# 01_Under_voltage_detection.net
KiCad netlist of a schematic drawn in Altium Designer
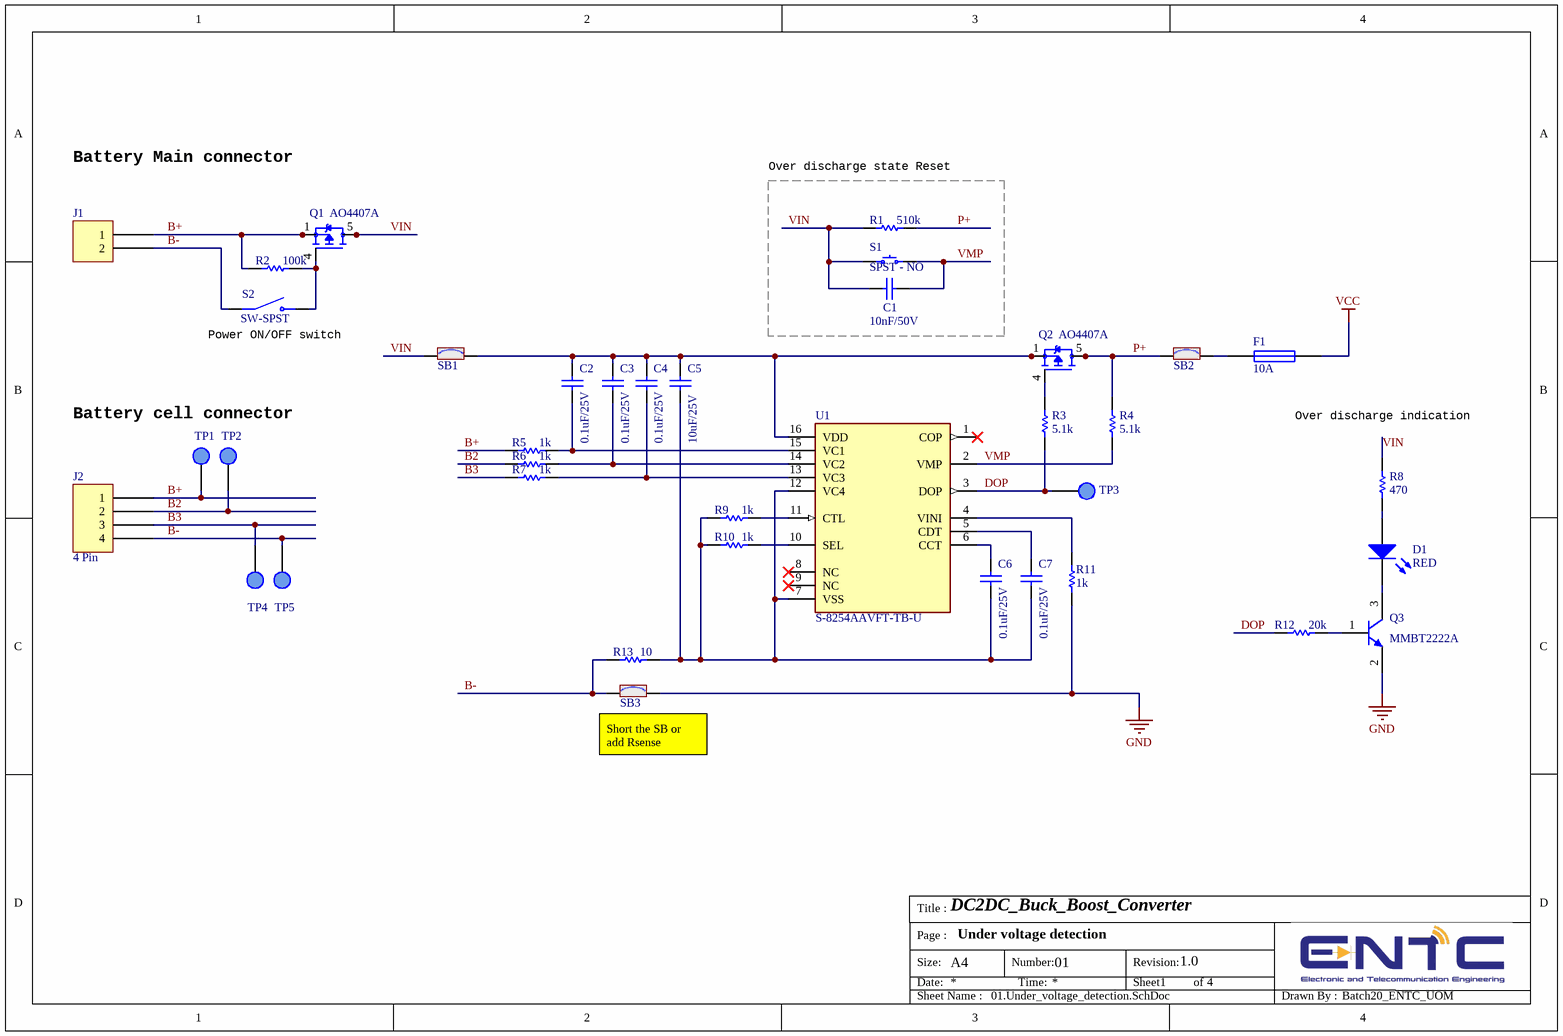
[diagram p0: 01.Under_voltage_detection.SchDoc]

(export (version "E")
  (design (tool "Eeschema 10.0.6"))
  (components
    (comp (ref "C1")
      (value "10nF/50V")
      (footprint "cap0805")
      (description "Multilayer Ceramic Capacitors MLCC - SMD/SMT 50V 0.01uF X7R 0805 10%")
      (fields (field (name "MF") "YAGEO") (field (name "MP") "CC0805KRX7R9BB103"))
      (libsource (lib "Altium_Main_Library") (part "Cap"))
    )
    (comp (ref "C2")
      (value "0.1uF/25V")
      (footprint "cap0805")
      (fields (field (name "MF") "KYOCERA AVX") (field (name "MP") "08053C104K4Z2A"))
      (libsource (lib "Altium_Main_Library") (part "Cap"))
    )
    (comp (ref "C3")
      (value "0.1uF/25V")
      (footprint "cap0805")
      (fields (field (name "MF") "KYOCERA AVX") (field (name "MP") "08053C104K4Z2A"))
      (libsource (lib "Altium_Main_Library") (part "Cap"))
    )
    (comp (ref "C4")
      (value "0.1uF/25V")
      (footprint "cap0805")
      (fields (field (name "MF") "KYOCERA AVX") (field (name "MP") "08053C104K4Z2A"))
      (libsource (lib "Altium_Main_Library") (part "Cap"))
    )
    (comp (ref "C5")
      (value "10uF/25V")
      (footprint "cap0805")
      (fields (field (name "MF") "KYOCERA AVX") (field (name "MP") "08053D106KAT4A"))
      (libsource (lib "Altium_Main_Library") (part "Cap"))
    )
    (comp (ref "C6")
      (value "0.1uF/25V")
      (footprint "cap0805")
      (fields (field (name "MF") "KYOCERA AVX") (field (name "MP") "08053C104K4Z2A"))
      (libsource (lib "Altium_Main_Library") (part "Cap"))
    )
    (comp (ref "C7")
      (value "0.1uF/25V")
      (footprint "cap0805")
      (fields (field (name "MF") "KYOCERA AVX") (field (name "MP") "08053C104K4Z2A"))
      (libsource (lib "Altium_Main_Library") (part "Cap"))
    )
    (comp (ref "D1")
      (value "RED")
      (footprint "LED0805")
      (description "Standard LEDs - SMD Super Red, 630nm 9mcd, 2mA")
      (fields (field (name "MF") "ams OSRAM") (field (name "MP") "LS M67K-H2K1-1-Z"))
      (libsource (lib "Altium_Main_Library") (part "LED"))
    )
    (comp (ref "F1")
      (value "10A")
      (footprint "FUSE_4245")
      (description "10A Glass fuse")
      (libsource (lib "Altium_Main_Library") (part "Fuse"))
    )
    (comp (ref "J1")
      (value "~")
      (footprint "JST XH B2B-XH-A")
      (description "CONN BARRIER STRIP 2CIRC 0.375\"")
      (libsource (lib "Altium_Main_Library") (part "2 Pin"))
    )
    (comp (ref "J2")
      (value "4 Pin")
      (footprint "JST XH B4B-XH-A")
      (description "JST Automotive Connectors XH HEADER (TOP)")
      (fields (field (name "MP") "B4B-XH-AM(LF)(SN)") (field (name "MF") "JST Commercial"))
      (libsource (lib "Altium_Main_Library") (part "4 Pin"))
    )
    (comp (ref "Q1")
      (value "AO4407A")
      (footprint "SOIC127P600X175-8N")
      (description "MOSFETs P-Channel 2.5W")
      (fields (field (name "MP") "DMP3020LSS-13") (field (name "MF") "Diodes Incorporated"))
      (libsource (lib "DC2DC_Buck_Boost_Converter_SchLib") (part "AO4407A"))
    )
    (comp (ref "Q2")
      (value "AO4407A")
      (footprint "SOIC127P600X175-8N")
      (description "MOSFETs P-Channel 2.5W")
      (fields (field (name "MP") "DMP3020LSS-13") (field (name "MF") "Diodes Incorporated"))
      (libsource (lib "DC2DC_Buck_Boost_Converter_SchLib") (part "AO4407A"))
    )
    (comp (ref "Q3")
      (value "MMBT2222A")
      (footprint "SOT23")
      (description "NPN Bipolar Transistor")
      (fields (field (name "MF") "Diotec Semiconductor"))
      (libsource (lib "Altium_Main_Library") (part "NPN"))
    )
    (comp (ref "R1")
      (value "510k")
      (footprint "RES0805")
      (description "Thick Film Resistors - SMD 510K 5%")
      (fields (field (name "MP") "CR0805-JW-514ELF") (field (name "MF") "Bourns"))
      (libsource (lib "Altium_Main_Library") (part "Res"))
    )
    (comp (ref "R2")
      (value "100k")
      (footprint "RES0805")
      (description "Thick Film Resistors - SMD 100K 5%")
      (fields (field (name "MP") "CR0805-JW-104ELF") (field (name "MF") "Bourns"))
      (libsource (lib "Altium_Main_Library") (part "Res"))
    )
    (comp (ref "R3")
      (value "5.1k")
      (footprint "RES0805")
      (description "Thick Film Resistors - SMD 5.1Kohms 1% 100ppm")
      (fields (field (name "MP") "RCA08055K10FKEA") (field (name "MF") "Vishay / Draloric"))
      (libsource (lib "Altium_Main_Library") (part "Res"))
    )
    (comp (ref "R4")
      (value "5.1k")
      (footprint "RES0805")
      (description "Thick Film Resistors - SMD 5.1Kohms 1% 100ppm")
      (fields (field (name "MP") "RCA08055K10FKEA") (field (name "MF") "Vishay / Draloric"))
      (libsource (lib "Altium_Main_Library") (part "Res"))
    )
    (comp (ref "R5")
      (value "1k")
      (footprint "RES0805")
      (description "Thick Film Resistors - SMD 1 kOhms 125 mW 0805 1%")
      (fields (field (name "MP") "RC0805FR-071KL") (field (name "MF") "YAGEO"))
      (libsource (lib "Altium_Main_Library") (part "Res"))
    )
    (comp (ref "R6")
      (value "1k")
      (footprint "RES0805")
      (description "Thick Film Resistors - SMD 1 kOhms 125 mW 0805 1%")
      (fields (field (name "MP") "RC0805FR-071KL") (field (name "MF") "YAGEO"))
      (libsource (lib "Altium_Main_Library") (part "Res"))
    )
    (comp (ref "R7")
      (value "1k")
      (footprint "RES0805")
      (description "Resistor 0805Thick Film Resistors - SMD 1 kOhms 125 mW 0805 1%")
      (fields (field (name "MP") "RC0805FR-071KL") (field (name "MF") "YAGEO"))
      (libsource (lib "Altium_Main_Library") (part "Res"))
    )
    (comp (ref "R8")
      (value "470")
      (footprint "RES0805")
      (description "Thick Film Resistors - SMD 470ohm 5%")
      (fields (field (name "MP") "CR0805-JW-471ELF") (field (name "MF") "Bourns"))
      (libsource (lib "Altium_Main_Library") (part "Res"))
    )
    (comp (ref "R9")
      (value "1k")
      (footprint "RES0805")
      (description "Resistor 0805")
      (fields (field (name "MP") "RC0805FR-071KL") (field (name "MF") "YAGEO"))
      (libsource (lib "Altium_Main_Library") (part "Res"))
    )
    (comp (ref "R10")
      (value "1k")
      (footprint "RES0805")
      (description "Resistor 0805")
      (fields (field (name "MP") "RC0805FR-071KL") (field (name "MF") "YAGEO"))
      (libsource (lib "Altium_Main_Library") (part "Res"))
    )
    (comp (ref "R11")
      (value "1k")
      (footprint "RES0805")
      (description "Thick Film Resistors - SMD 1 kOhms 125 mW 0805 1%")
      (fields (field (name "MP") "RC0805FR-071KL") (field (name "MF") "YAGEO"))
      (libsource (lib "Altium_Main_Library") (part "Res"))
    )
    (comp (ref "R12")
      (value "20k")
      (footprint "RES0805")
      (description "Thick Film Resistors - SMD 20K 1%")
      (fields (field (name "MP") "CR0805-FX-2002ELF") (field (name "MF") "Bourns"))
      (libsource (lib "Altium_Main_Library") (part "Res"))
    )
    (comp (ref "R13")
      (value "10")
      (footprint "RES0805")
      (description "Thin Film Resistors - SMD 10 ohm 1% 50 ppm Thin Film")
      (fields (field (name "MP") "RT0805FRE1310RL") (field (name "MF") "YAGEO"))
      (libsource (lib "Altium_Main_Library") (part "Res"))
    )
    (comp (ref "S1")
      (value "SPST - NO")
      (footprint "4312560387x6")
      (description "Switch Push button")
      (libsource (lib "DC2DC_Buck_Boost_Converter_SchLib") (part "SPST-NO 4 PIN"))
    )
    (comp (ref "S2")
      (value "SW-SPST")
      (footprint "SW_TL2230EEF100")
      (libsource (lib "DC2DC_Buck_Boost_Converter_SchLib") (part "SW-SPST"))
    )
    (comp (ref "SB1")
      (value "SB_ON")
      (footprint "SOLDER-BRIDGE_R0805-0R")
      (description "Solder Bridge ON")
      (fields (field (name "MP") "CR0805AJ/-000EAS") (field (name "MF") "Bourns"))
      (libsource (lib "Altium_Main_Library") (part "SB_ON"))
    )
    (comp (ref "SB2")
      (value "SB_ON")
      (footprint "SOLDER-BRIDGE_R0805-0R")
      (description "Solder Bridge ON")
      (fields (field (name "MP") "CR0805AJ/-000EAS") (field (name "MF") "Bourns"))
      (libsource (lib "Altium_Main_Library") (part "SB_ON"))
    )
    (comp (ref "SB3")
      (value "SB_ON")
      (footprint "SOLDER-BRIDGE_R0805-0R")
      (description "Solder Bridge ON")
      (fields (field (name "MP") "CR0805AJ/-000EAS") (field (name "MF") "Bourns"))
      (libsource (lib "Altium_Main_Library") (part "SB_ON"))
    )
    (comp (ref "TP1")
      (value "~")
      (footprint "tp")
      (description "Test Point")
      (libsource (lib "Altium_Main_Library") (part "TP"))
    )
    (comp (ref "TP2")
      (value "~")
      (footprint "tp")
      (description "Test Point")
      (libsource (lib "Altium_Main_Library") (part "TP"))
    )
    (comp (ref "TP3")
      (value "~")
      (footprint "tp")
      (description "Test Point")
      (libsource (lib "Altium_Main_Library") (part "TP"))
    )
    (comp (ref "TP4")
      (value "~")
      (footprint "tp")
      (description "Test Point")
      (libsource (lib "Altium_Main_Library") (part "TP"))
    )
    (comp (ref "TP5")
      (value "~")
      (footprint "tp")
      (description "Test Point")
      (libsource (lib "Altium_Main_Library") (part "TP"))
    )
    (comp (ref "U1")
      (value "S-8254AAVFT-TB-U")
      (footprint "SOP65P640X110-16N:SOP65P640X110-16N")
      (description "Battery Management LITHIUM-ION BATTERY PROTECTION 3/4 CELL")
      (fields (field (name "MF") "ABLIC"))
      (libsource (lib "DC2DC_Buck_Boost_Converter_SchLib") (part "S-8254AAEFT-TB-G"))
    )
  )
  (nets
    (net (code "1") (name "/B+") (class "Default")
      (node (ref "J1") (pin "1") (pinfunction "1_1") (pintype "passive"))
      (node (ref "J2") (pin "1") (pinfunction "1_1") (pintype "passive"))
      (node (ref "Q1") (pin "1") (pinfunction "S_1") (pintype "passive"))
      (node (ref "Q1") (pin "2") (pinfunction "S_2") (pintype "passive"))
      (node (ref "Q1") (pin "3") (pinfunction "S_3") (pintype "passive"))
      (node (ref "R2") (pin "1") (pinfunction "1_1") (pintype "passive"))
      (node (ref "R5") (pin "1") (pinfunction "1_1") (pintype "passive"))
      (node (ref "TP1") (pin "1") (pinfunction "___TP_1") (pintype "passive"))
    )
    (net (code "2") (name "/B-") (class "Default")
      (node (ref "J1") (pin "2") (pinfunction "2_2") (pintype "passive"))
      (node (ref "J2") (pin "4") (pinfunction "4_4") (pintype "passive"))
      (node (ref "R13") (pin "1") (pinfunction "1_1") (pintype "passive"))
      (node (ref "S2") (pin "2") (pinfunction "COM_2") (pintype "passive"))
      (node (ref "SB3") (pin "1") (pinfunction "1_1") (pintype "passive"))
      (node (ref "TP5") (pin "1") (pinfunction "___TP_1") (pintype "passive"))
    )
    (net (code "3") (name "/B2") (class "Default")
      (node (ref "J2") (pin "2") (pinfunction "2_2") (pintype "passive"))
      (node (ref "R6") (pin "1") (pinfunction "1_1") (pintype "passive"))
      (node (ref "TP2") (pin "1") (pinfunction "___TP_1") (pintype "passive"))
    )
    (net (code "4") (name "/B3") (class "Default")
      (node (ref "J2") (pin "3") (pinfunction "3_3") (pintype "passive"))
      (node (ref "R7") (pin "1") (pinfunction "1_1") (pintype "passive"))
      (node (ref "TP4") (pin "1") (pinfunction "___TP_1") (pintype "passive"))
    )
    (net (code "5") (name "/DOP") (class "Default")
      (node (ref "R12") (pin "2") (pinfunction "2_2") (pintype "passive"))
      (node (ref "R3") (pin "1") (pinfunction "1_1") (pintype "passive"))
      (node (ref "TP3") (pin "1") (pinfunction "___TP_1") (pintype "passive"))
      (node (ref "U1") (pin "3") (pinfunction "DOP_3") (pintype "output"))
    )
    (net (code "6") (name "/P+") (class "Default")
      (node (ref "Q2") (pin "5") (pinfunction "D_5") (pintype "passive"))
      (node (ref "Q2") (pin "6") (pinfunction "D_6") (pintype "passive"))
      (node (ref "Q2") (pin "7") (pinfunction "D_7") (pintype "passive"))
      (node (ref "Q2") (pin "8") (pinfunction "D_8") (pintype "passive"))
      (node (ref "R1") (pin "1") (pinfunction "1_1") (pintype "passive"))
      (node (ref "R4") (pin "2") (pinfunction "2_2") (pintype "passive"))
      (node (ref "SB2") (pin "1") (pinfunction "1_1") (pintype "passive"))
    )
    (net (code "7") (name "/VIN") (class "Default")
      (node (ref "C1") (pin "2") (pinfunction "2_2") (pintype "passive"))
      (node (ref "Q1") (pin "5") (pinfunction "D_5") (pintype "passive"))
      (node (ref "Q1") (pin "6") (pinfunction "D_6") (pintype "passive"))
      (node (ref "Q1") (pin "7") (pinfunction "D_7") (pintype "passive"))
      (node (ref "Q1") (pin "8") (pinfunction "D_8") (pintype "passive"))
      (node (ref "R1") (pin "2") (pinfunction "2_2") (pintype "passive"))
      (node (ref "R8") (pin "2") (pinfunction "2_2") (pintype "passive"))
      (node (ref "S1") (pin "1") (pinfunction "1_1") (pintype "passive"))
      (node (ref "SB1") (pin "1") (pinfunction "1_1") (pintype "passive"))
    )
    (net (code "8") (name "/VMP") (class "Default")
      (node (ref "C1") (pin "1") (pinfunction "1_1") (pintype "passive"))
      (node (ref "R4") (pin "1") (pinfunction "1_1") (pintype "passive"))
      (node (ref "S1") (pin "2") (pinfunction "2_2") (pintype "passive"))
      (node (ref "U1") (pin "2") (pinfunction "VMP_2") (pintype "passive"))
    )
    (net (code "9") (name "GND") (class "Default")
      (node (ref "Q3") (pin "2") (pinfunction "E_2") (pintype "passive"))
      (node (ref "R11") (pin "1") (pinfunction "1_1") (pintype "passive"))
      (node (ref "SB3") (pin "2") (pinfunction "2_2") (pintype "passive"))
    )
    (net (code "10") (name "Net-(D1-A)") (class "Default")
      (node (ref "D1") (pin "1") (pinfunction "A_1") (pintype "passive"))
      (node (ref "R8") (pin "1") (pinfunction "1_1") (pintype "passive"))
    )
    (net (code "11") (name "Net-(D1-K)") (class "Default")
      (node (ref "D1") (pin "2") (pinfunction "K_2") (pintype "passive"))
      (node (ref "Q3") (pin "3") (pinfunction "C_3") (pintype "passive"))
    )
    (net (code "12") (name "Net-(F1-Pad1)") (class "Default")
      (node (ref "F1") (pin "1") (pinfunction "1_1") (pintype "passive"))
      (node (ref "SB2") (pin "2") (pinfunction "2_2") (pintype "passive"))
    )
    (net (code "13") (name "Net-(Q1-G)") (class "Default")
      (node (ref "Q1") (pin "4") (pinfunction "G_4") (pintype "passive"))
      (node (ref "R2") (pin "2") (pinfunction "2_2") (pintype "passive"))
      (node (ref "S2") (pin "3") (pinfunction "NO_3") (pintype "passive"))
    )
    (net (code "14") (name "Net-(Q2-G)") (class "Default")
      (node (ref "Q2") (pin "4") (pinfunction "G_4") (pintype "passive"))
      (node (ref "R3") (pin "2") (pinfunction "2_2") (pintype "passive"))
    )
    (net (code "15") (name "Net-(Q3-B)") (class "Default")
      (node (ref "Q3") (pin "1") (pinfunction "B_1") (pintype "passive"))
      (node (ref "R12") (pin "1") (pinfunction "1_1") (pintype "passive"))
    )
    (net (code "16") (name "Net-(U1-CCT)") (class "Default")
      (node (ref "C6") (pin "2") (pinfunction "2_2") (pintype "passive"))
      (node (ref "U1") (pin "6") (pinfunction "CCT_6") (pintype "passive"))
    )
    (net (code "17") (name "Net-(U1-CDT)") (class "Default")
      (node (ref "C7") (pin "2") (pinfunction "2_2") (pintype "passive"))
      (node (ref "U1") (pin "5") (pinfunction "CDT_5") (pintype "passive"))
    )
    (net (code "18") (name "Net-(U1-CTL)") (class "Default")
      (node (ref "R9") (pin "2") (pinfunction "2_2") (pintype "passive"))
      (node (ref "U1") (pin "11") (pinfunction "CTL_11") (pintype "input"))
    )
    (net (code "19") (name "Net-(U1-SEL)") (class "Default")
      (node (ref "R10") (pin "2") (pinfunction "2_2") (pintype "passive"))
      (node (ref "U1") (pin "10") (pinfunction "SEL_10") (pintype "passive"))
    )
    (net (code "20") (name "Net-(U1-VC1)") (class "Default")
      (node (ref "C2") (pin "1") (pinfunction "1_1") (pintype "passive"))
      (node (ref "R5") (pin "2") (pinfunction "2_2") (pintype "passive"))
      (node (ref "U1") (pin "15") (pinfunction "VC1_15") (pintype "power_in"))
    )
    (net (code "21") (name "Net-(U1-VC2)") (class "Default")
      (node (ref "C3") (pin "1") (pinfunction "1_1") (pintype "passive"))
      (node (ref "R6") (pin "2") (pinfunction "2_2") (pintype "passive"))
      (node (ref "U1") (pin "14") (pinfunction "VC2_14") (pintype "power_in"))
    )
    (net (code "22") (name "Net-(U1-VC3)") (class "Default")
      (node (ref "C4") (pin "1") (pinfunction "1_1") (pintype "passive"))
      (node (ref "R7") (pin "2") (pinfunction "2_2") (pintype "passive"))
      (node (ref "U1") (pin "13") (pinfunction "VC3_13") (pintype "power_in"))
    )
    (net (code "23") (name "Net-(U1-VC4)") (class "Default")
      (node (ref "C5") (pin "1") (pinfunction "1_1") (pintype "passive"))
      (node (ref "C6") (pin "1") (pinfunction "1_1") (pintype "passive"))
      (node (ref "C7") (pin "1") (pinfunction "1_1") (pintype "passive"))
      (node (ref "R10") (pin "1") (pinfunction "1_1") (pintype "passive"))
      (node (ref "R13") (pin "2") (pinfunction "2_2") (pintype "passive"))
      (node (ref "R9") (pin "1") (pinfunction "1_1") (pintype "passive"))
      (node (ref "U1") (pin "12") (pinfunction "VC4_12") (pintype "power_in"))
      (node (ref "U1") (pin "7") (pinfunction "VSS_7") (pintype "power_in"))
    )
    (net (code "24") (name "Net-(U1-VDD)") (class "Default")
      (node (ref "C2") (pin "2") (pinfunction "2_2") (pintype "passive"))
      (node (ref "C3") (pin "2") (pinfunction "2_2") (pintype "passive"))
      (node (ref "C4") (pin "2") (pinfunction "2_2") (pintype "passive"))
      (node (ref "C5") (pin "2") (pinfunction "2_2") (pintype "passive"))
      (node (ref "Q2") (pin "1") (pinfunction "S_1") (pintype "passive"))
      (node (ref "Q2") (pin "2") (pinfunction "S_2") (pintype "passive"))
      (node (ref "Q2") (pin "3") (pinfunction "S_3") (pintype "passive"))
      (node (ref "SB1") (pin "2") (pinfunction "2_2") (pintype "passive"))
      (node (ref "U1") (pin "16") (pinfunction "VDD_16") (pintype "power_in"))
    )
    (net (code "25") (name "Net-(U1-VINI)") (class "Default")
      (node (ref "R11") (pin "2") (pinfunction "2_2") (pintype "passive"))
      (node (ref "U1") (pin "4") (pinfunction "VINI_4") (pintype "passive"))
    )
    (net (code "26") (name "VCC") (class "Default")
      (node (ref "F1") (pin "2") (pinfunction "2_2") (pintype "passive"))
    )
    (net (code "27") (name "unconnected-(U1-COP-Pad1)") (class "Default")
      (node (ref "U1") (pin "1") (pinfunction "COP_1") (pintype "output+no_connect"))
    )
    (net (code "28") (name "unconnected-(U1-NC-Pad8)") (class "Default")
      (node (ref "U1") (pin "8") (pinfunction "NC_8") (pintype "passive+no_connect"))
    )
    (net (code "29") (name "unconnected-(U1-NC-Pad9)") (class "Default")
      (node (ref "U1") (pin "9") (pinfunction "NC_9") (pintype "passive+no_connect"))
    )
  )
)
